# CarPC-CC-Rev3.net
KiCad netlist of a schematic drawn in EAGLE
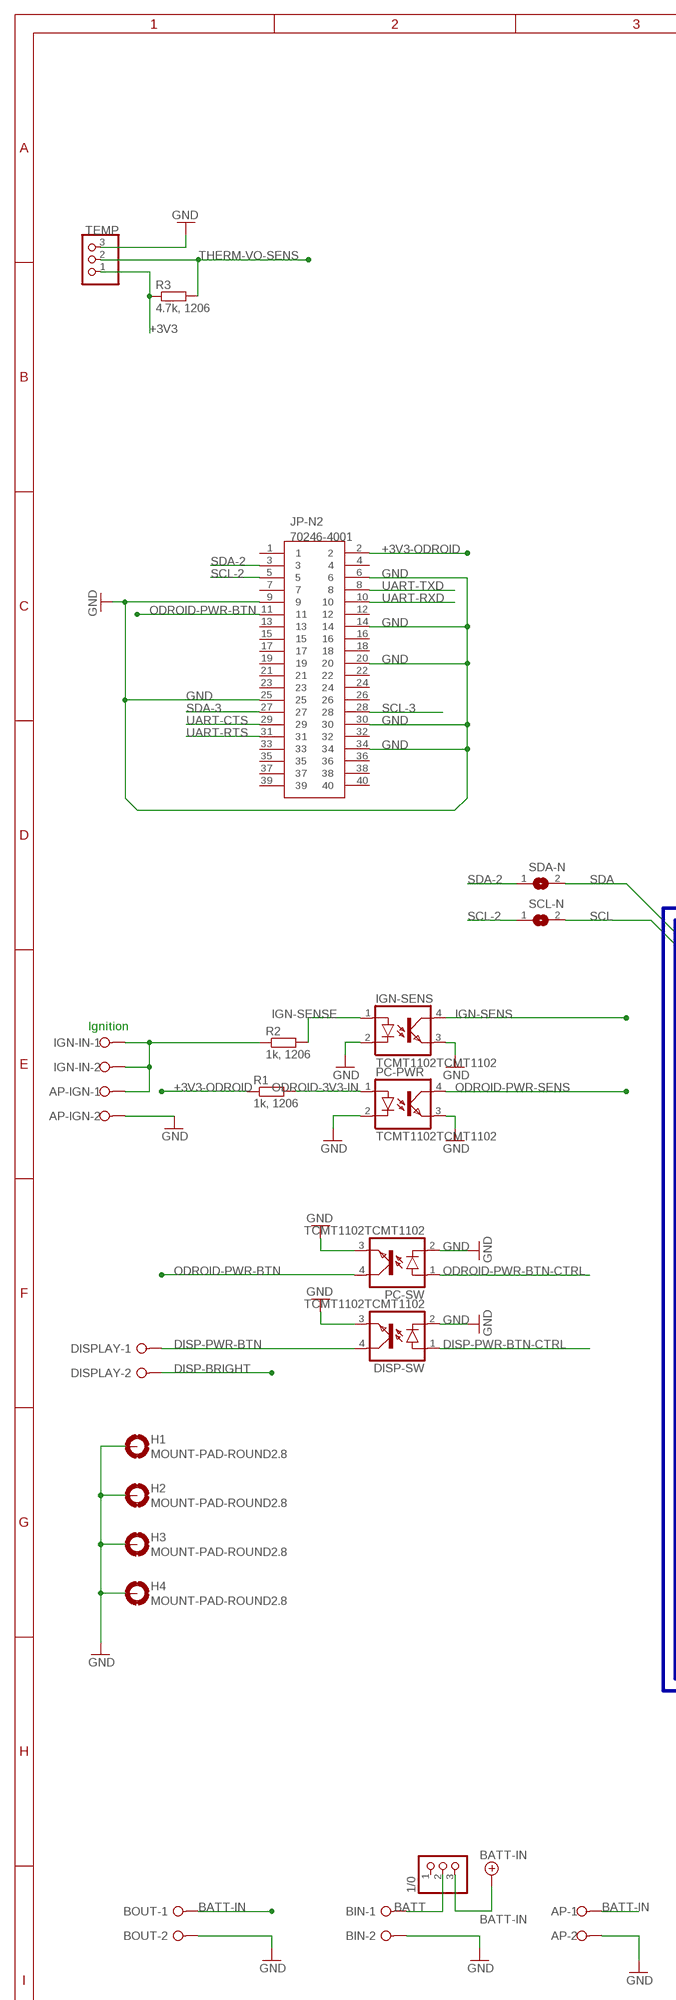
[diagram p0: schematic, sheet 1, part 1 of 2]
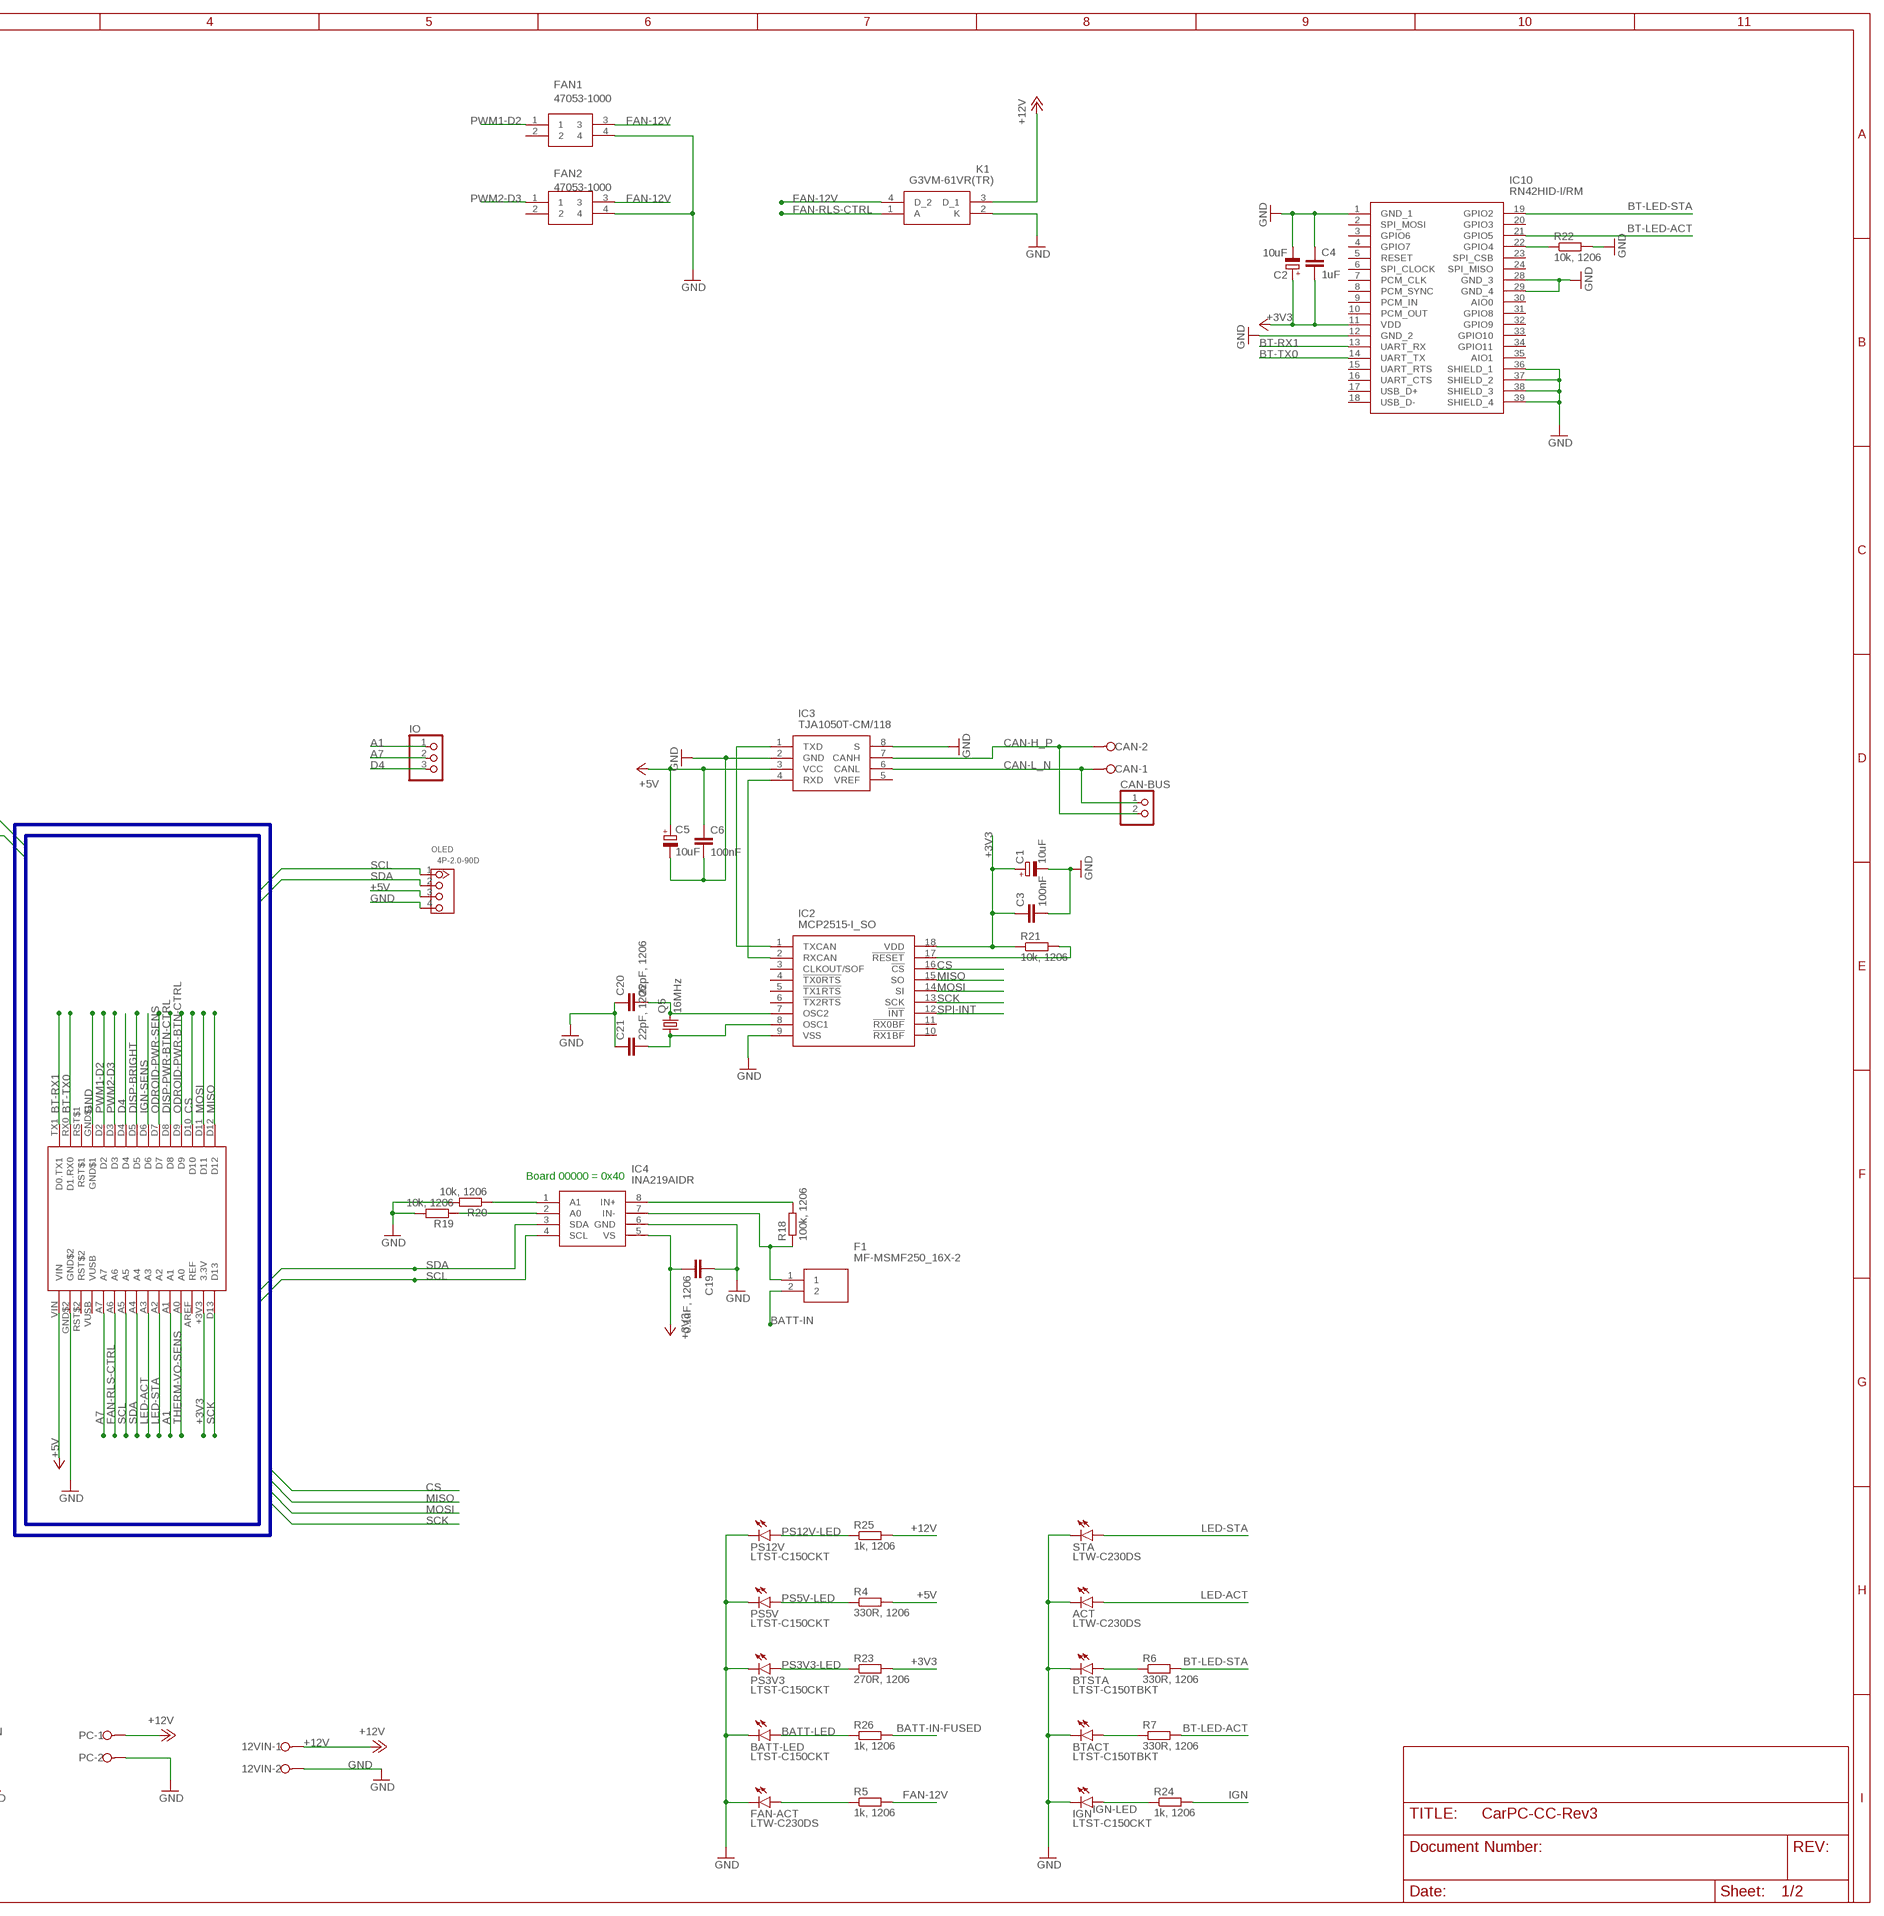
[diagram p1: schematic, sheet 1, part 2 of 2]
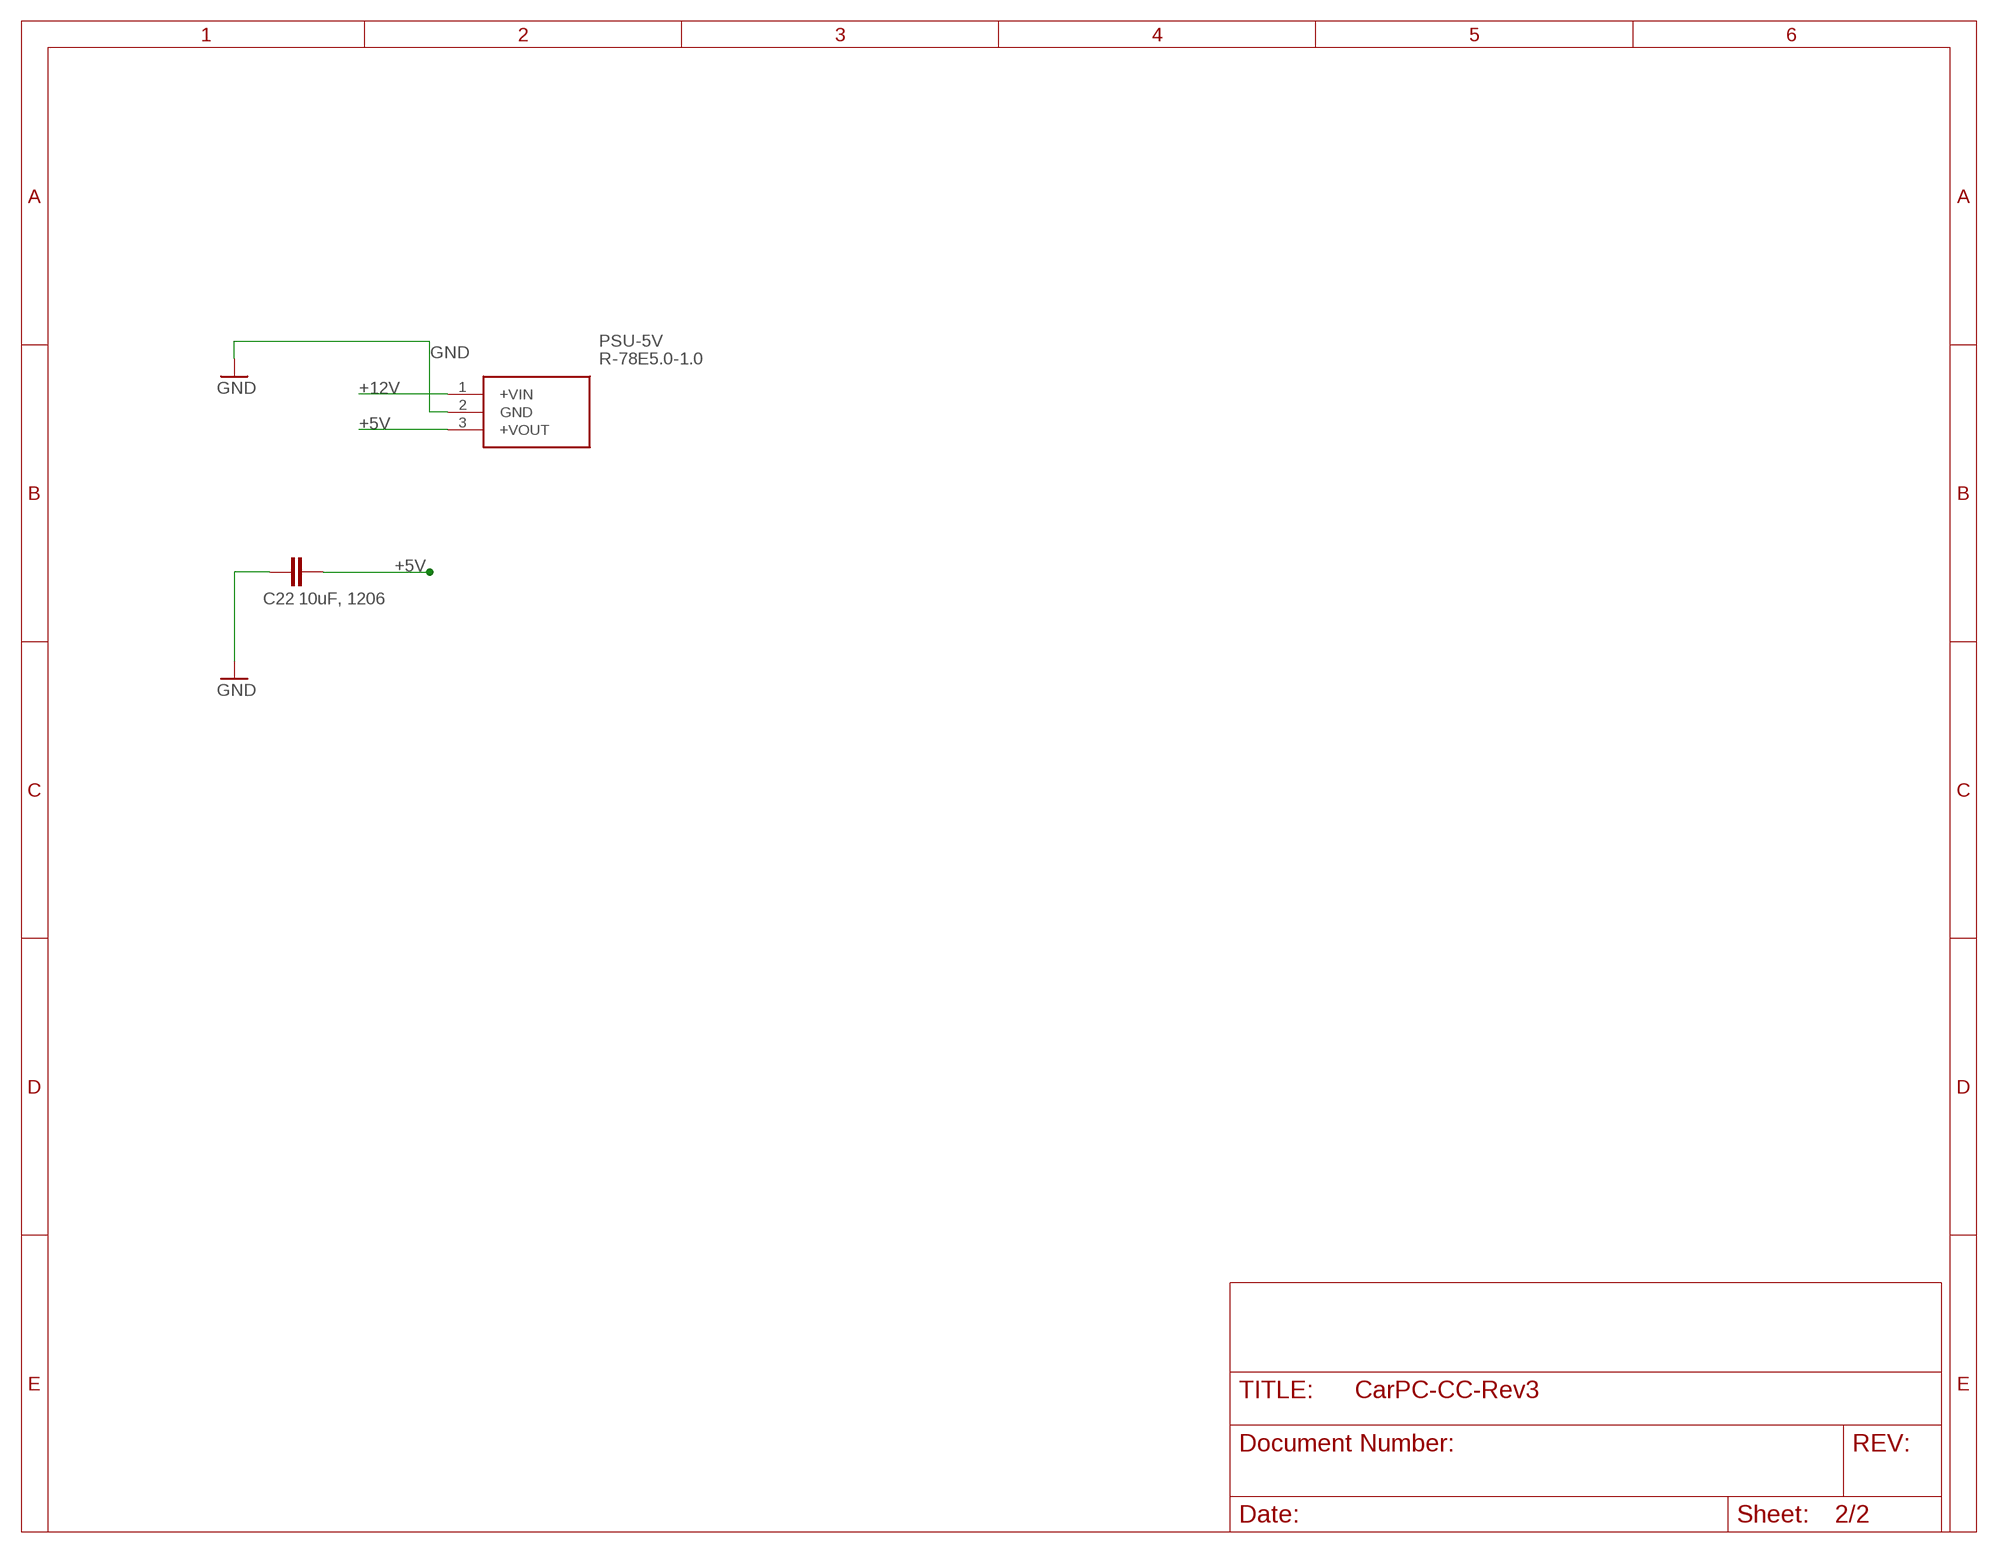
[diagram p2: schematic, sheet 2]

(export (version "E")
  (design (tool "Eeschema 10.0.6"))
  (components
    (comp (ref "1/0")
      (value "PINHD-1X3")
      (footprint "eagle-import:1X03")
      (libsource (lib "eagle-import") (part "PINHD-1X3"))
    )
    (comp (ref "12VIN")
      (value "W237-02P")
      (footprint "eagle-import:W237_132")
      (libsource (lib "eagle-import") (part "W237-02P"))
    )
    (comp (ref "ACT")
      (value "LTW-C230DS")
      (footprint "eagle-import:CHIPLED_1206")
      (libsource (lib "eagle-import") (part "LEDCHIPLED_1206"))
    )
    (comp (ref "AP")
      (value "W237-02P")
      (footprint "eagle-import:W237_132")
      (libsource (lib "eagle-import") (part "W237-02P"))
    )
    (comp (ref "AP-IGN")
      (value "W237-02P")
      (footprint "eagle-import:W237_132")
      (libsource (lib "eagle-import") (part "W237-02P"))
    )
    (comp (ref "BATT-LED")
      (value "LTST-C150CKT")
      (footprint "eagle-import:CHIPLED_1206")
      (libsource (lib "eagle-import") (part "LEDCHIPLED_1206"))
    )
    (comp (ref "BIN")
      (value "W237-02P")
      (footprint "eagle-import:W237_132")
      (libsource (lib "eagle-import") (part "W237-02P"))
    )
    (comp (ref "BOUT")
      (value "W237-02P")
      (footprint "eagle-import:W237_132")
      (libsource (lib "eagle-import") (part "W237-02P"))
    )
    (comp (ref "BTACT")
      (value "LTST-C150TBKT")
      (footprint "eagle-import:CHIPLED_1206")
      (libsource (lib "eagle-import") (part "LEDCHIPLED_1206"))
    )
    (comp (ref "BTSTA")
      (value "LTST-C150TBKT")
      (footprint "eagle-import:CHIPLED_1206")
      (libsource (lib "eagle-import") (part "LEDCHIPLED_1206"))
    )
    (comp (ref "C1")
      (value "10uF")
      (footprint "eagle-import:C1206")
      (libsource (lib "eagle-import") (part "CPOL-1206"))
    )
    (comp (ref "C2")
      (value "10uF")
      (footprint "eagle-import:C1206")
      (libsource (lib "eagle-import") (part "CPOL-1206"))
    )
    (comp (ref "C3")
      (value "100nF")
      (footprint "eagle-import:C1206")
      (libsource (lib "eagle-import") (part "C-EUC1206"))
    )
    (comp (ref "C4")
      (value "1uF")
      (footprint "eagle-import:C1206")
      (libsource (lib "eagle-import") (part "C-EUC1206"))
    )
    (comp (ref "C5")
      (value "10uF")
      (footprint "eagle-import:C1206")
      (libsource (lib "eagle-import") (part "CPOL-1206"))
    )
    (comp (ref "C6")
      (value "100nF")
      (footprint "eagle-import:C1206")
      (libsource (lib "eagle-import") (part "C-EUC1206"))
    )
    (comp (ref "C19")
      (value "0.1uF, 1206")
      (footprint "eagle-import:C1206")
      (libsource (lib "eagle-import") (part "C-EUC1206"))
    )
    (comp (ref "C20")
      (value "22pF, 1206")
      (footprint "eagle-import:C1206")
      (libsource (lib "eagle-import") (part "C-EUC1206"))
    )
    (comp (ref "C21")
      (value "22pF, 1206")
      (footprint "eagle-import:C1206")
      (libsource (lib "eagle-import") (part "C-EUC1206"))
    )
    (comp (ref "CAN")
      (value "W237-02P")
      (footprint "eagle-import:W237_132")
      (libsource (lib "eagle-import") (part "W237-02P"))
    )
    (comp (ref "CAN-BUS")
      (value "PINHD-1X2")
      (footprint "eagle-import:1X02")
      (libsource (lib "eagle-import") (part "PINHD-1X2"))
    )
    (comp (ref "DISP-SW")
      (value "TCMT1102TCMT1102")
      (footprint "eagle-import:SOIC127P700X230-4N")
      (libsource (lib "eagle-import") (part "TCMT1102TCMT1102"))
    )
    (comp (ref "DISPLAY")
      (value "W237-02P")
      (footprint "eagle-import:W237_132")
      (libsource (lib "eagle-import") (part "W237-02P"))
    )
    (comp (ref "F1")
      (value "MF-MSMF250_16X-2")
      (footprint "eagle-import:FUSC4632X160N")
      (fields
        (field (name "MANUFACTURER_PART_NUMBER") "MF-MSMF250/16X-2")
        (field (name "MOUSER_PART_NUMBER") "652-MF-MSMF250/16X-2")
        (field (name "RS_PART_NUMBER") "8978967P")
      )
      (libsource (lib "eagle-import") (part "MF-MSMF250_16X-2"))
    )
    (comp (ref "FAN-ACT")
      (value "LTW-C230DS")
      (footprint "eagle-import:CHIPLED_1206")
      (libsource (lib "eagle-import") (part "LEDCHIPLED_1206"))
    )
    (comp (ref "FAN1")
      (value "47053-1000")
      (footprint "eagle-import:47053-1000")
      (fields (field (name "MOUSER_PART_NUMBER") "538-47053-1000"))
      (libsource (lib "eagle-import") (part "47053-1000"))
    )
    (comp (ref "FAN2")
      (value "47053-1000")
      (footprint "eagle-import:47053-1000")
      (fields (field (name "MOUSER_PART_NUMBER") "538-47053-1000"))
      (libsource (lib "eagle-import") (part "47053-1000"))
    )
    (comp (ref "H1")
      (value "MOUNT-PAD-ROUND2.8")
      (footprint "eagle-import:2,8-PAD")
      (libsource (lib "eagle-import") (part "MOUNT-PAD-ROUND2.8"))
    )
    (comp (ref "H2")
      (value "MOUNT-PAD-ROUND2.8")
      (footprint "eagle-import:2,8-PAD")
      (libsource (lib "eagle-import") (part "MOUNT-PAD-ROUND2.8"))
    )
    (comp (ref "H3")
      (value "MOUNT-PAD-ROUND2.8")
      (footprint "eagle-import:2,8-PAD")
      (libsource (lib "eagle-import") (part "MOUNT-PAD-ROUND2.8"))
    )
    (comp (ref "H4")
      (value "MOUNT-PAD-ROUND2.8")
      (footprint "eagle-import:2,8-PAD")
      (libsource (lib "eagle-import") (part "MOUNT-PAD-ROUND2.8"))
    )
    (comp (ref "IC2")
      (value "MCP2515-I_SO")
      (footprint "eagle-import:SOIC127P1030X265-18N")
      (fields
        (field (name "MANUFACTURER_PART_NUMBER") "MCP2515-I/SO")
        (field (name "MOUSER_PART_NUMBER") "579-MCP2515-I/SO")
      )
      (libsource (lib "eagle-import") (part "MCP2515-I_SO"))
    )
    (comp (ref "IC3")
      (value "TJA1050T-CM/118")
      (footprint "eagle-import:SOIC127P600X175-8N")
      (fields
        (field (name "MANUFACTURER_PART_NUMBER") "TJA1050T/CM,118")
        (field (name "MOUSER_PART_NUMBER") "771-TJA1050T/CM118")
      )
      (libsource (lib "eagle-import") (part "TJA1050T_CM,118"))
    )
    (comp (ref "IC4")
      (value "INA219AIDR")
      (footprint "eagle-import:SOIC127P600X175-8N")
      (fields (field (name "MOUSER_PART_NUMBER") "595-INA219AIDR"))
      (libsource (lib "eagle-import") (part "INA219AIDR"))
    )
    (comp (ref "IC10")
      (value "RN42HID-I/RM")
      (footprint "eagle-import:RN42HIDIRM")
      (fields
        (field (name "MOUSER_PART_NUMBER") "765-RN42HID-I/RM")
        (field (name "RS_PART_NUMBER") "9123020")
      )
      (libsource (lib "eagle-import") (part "RN42HID-I_RM"))
    )
    (comp (ref "IGN")
      (value "LTST-C150CKT")
      (footprint "eagle-import:CHIPLED_1206")
      (libsource (lib "eagle-import") (part "LEDCHIPLED_1206"))
    )
    (comp (ref "IGN-IN")
      (value "W237-02P")
      (footprint "eagle-import:W237_132")
      (libsource (lib "eagle-import") (part "W237-02P"))
    )
    (comp (ref "IGN-SENS")
      (value "TCMT1102TCMT1102")
      (footprint "eagle-import:SOIC127P700X230-4N")
      (libsource (lib "eagle-import") (part "TCMT1102TCMT1102"))
    )
    (comp (ref "IO")
      (value "PINHD-1X3")
      (footprint "eagle-import:1X03")
      (libsource (lib "eagle-import") (part "PINHD-1X3"))
    )
    (comp (ref "JP-N2")
      (value "70246-4001")
      (footprint "eagle-import:SHDR40W94P254_2X20_5842X889X92")
      (fields (field (name "MOUSER_PART_NUMBER") "538-70246-4001") (field (name "RS_PART_NUMBER") "6701825P"))
      (libsource (lib "eagle-import") (part "70246-4001"))
    )
    (comp (ref "K1")
      (value "G3VM-61VR(TR)")
      (footprint "eagle-import:G3VM61VRTR")
      (fields (field (name "MOUSER_PART_NUMBER") "653-G3VM-61VRTR"))
      (libsource (lib "eagle-import") (part "G3VM-61VR(TR)"))
    )
    (comp (ref "NANO_33_IOT")
      (value "Arduino-Nano-33-IOT")
      (footprint "eagle-import:ARDNANO33IOT_SMD")
      (libsource (lib "eagle-import") (part "ARDUINONANO33IOTARDUINONANO33IOT_SMD"))
    )
    (comp (ref "OLED")
      (value "4P-2.0-90D")
      (footprint "eagle-import:HW4-2.0-90D")
      (libsource (lib "eagle-import") (part "GROVE-CONNECTOR-DIP-90D(4P-2.0)"))
    )
    (comp (ref "PC")
      (value "W237-02P")
      (footprint "eagle-import:W237_132")
      (libsource (lib "eagle-import") (part "W237-02P"))
    )
    (comp (ref "PC-PWR")
      (value "TCMT1102TCMT1102")
      (footprint "eagle-import:SOIC127P700X230-4N")
      (libsource (lib "eagle-import") (part "TCMT1102TCMT1102"))
    )
    (comp (ref "PC-SW")
      (value "TCMT1102TCMT1102")
      (footprint "eagle-import:SOIC127P700X230-4N")
      (libsource (lib "eagle-import") (part "TCMT1102TCMT1102"))
    )
    (comp (ref "PS3V3")
      (value "LTST-C150CKT")
      (footprint "eagle-import:CHIPLED_1206")
      (libsource (lib "eagle-import") (part "LEDCHIPLED_1206"))
    )
    (comp (ref "PS5V")
      (value "LTST-C150CKT")
      (footprint "eagle-import:CHIPLED_1206")
      (libsource (lib "eagle-import") (part "LEDCHIPLED_1206"))
    )
    (comp (ref "PS12V")
      (value "LTST-C150CKT")
      (footprint "eagle-import:CHIPLED_1206")
      (libsource (lib "eagle-import") (part "LEDCHIPLED_1206"))
    )
    (comp (ref "Q5")
      (value "16MHz")
      (footprint "eagle-import:HC49-S")
      (libsource (lib "eagle-import") (part "CRYSTALHC49S"))
    )
    (comp (ref "R1")
      (value "1k, 1206")
      (footprint "eagle-import:R1206")
      (libsource (lib "eagle-import") (part "R-EU_R1206"))
    )
    (comp (ref "R2")
      (value "1k, 1206")
      (footprint "eagle-import:R1206")
      (libsource (lib "eagle-import") (part "R-EU_R1206"))
    )
    (comp (ref "R3")
      (value "4.7k, 1206")
      (footprint "eagle-import:R1206")
      (libsource (lib "eagle-import") (part "R-EU_R1206"))
    )
    (comp (ref "R4")
      (value "330R, 1206")
      (footprint "eagle-import:R1206")
      (libsource (lib "eagle-import") (part "R-EU_R1206"))
    )
    (comp (ref "R5")
      (value "1k, 1206")
      (footprint "eagle-import:R1206")
      (libsource (lib "eagle-import") (part "R-EU_R1206"))
    )
    (comp (ref "R6")
      (value "330R, 1206")
      (footprint "eagle-import:R1206")
      (libsource (lib "eagle-import") (part "R-EU_R1206"))
    )
    (comp (ref "R7")
      (value "330R, 1206")
      (footprint "eagle-import:R1206")
      (libsource (lib "eagle-import") (part "R-EU_R1206"))
    )
    (comp (ref "R18")
      (value "100k, 1206")
      (footprint "eagle-import:R1206")
      (libsource (lib "eagle-import") (part "R-EU_R1206"))
    )
    (comp (ref "R19")
      (value "10k, 1206")
      (footprint "eagle-import:R1206")
      (libsource (lib "eagle-import") (part "R-EU_R1206"))
    )
    (comp (ref "R20")
      (value "10k, 1206")
      (footprint "eagle-import:R1206")
      (libsource (lib "eagle-import") (part "R-EU_R1206"))
    )
    (comp (ref "R21")
      (value "10k, 1206")
      (footprint "eagle-import:R1206")
      (libsource (lib "eagle-import") (part "R-EU_R1206"))
    )
    (comp (ref "R22")
      (value "10k, 1206")
      (footprint "eagle-import:R1206")
      (libsource (lib "eagle-import") (part "R-EU_R1206"))
    )
    (comp (ref "R23")
      (value "270R, 1206")
      (footprint "eagle-import:R1206")
      (libsource (lib "eagle-import") (part "R-EU_R1206"))
    )
    (comp (ref "R24")
      (value "1k, 1206")
      (footprint "eagle-import:R1206")
      (libsource (lib "eagle-import") (part "R-EU_R1206"))
    )
    (comp (ref "R25")
      (value "1k, 1206")
      (footprint "eagle-import:R1206")
      (libsource (lib "eagle-import") (part "R-EU_R1206"))
    )
    (comp (ref "R26")
      (value "1k, 1206")
      (footprint "eagle-import:R1206")
      (libsource (lib "eagle-import") (part "R-EU_R1206"))
    )
    (comp (ref "SCL-N")
      (value "SJ")
      (footprint "eagle-import:SJ")
      (libsource (lib "eagle-import") (part "SJ"))
    )
    (comp (ref "SDA-N")
      (value "SJ")
      (footprint "eagle-import:SJ")
      (libsource (lib "eagle-import") (part "SJ"))
    )
    (comp (ref "STA")
      (value "LTW-C230DS")
      (footprint "eagle-import:CHIPLED_1206")
      (libsource (lib "eagle-import") (part "LEDCHIPLED_1206"))
    )
    (comp (ref "TEMP")
      (value "PINHD-1X3/90")
      (footprint "eagle-import:1X03_90")
      (libsource (lib "eagle-import") (part "PINHD-1X3/90"))
    )
    (comp (ref "C22")
      (value "10uF, 1206")
      (footprint "eagle-import:C1206")
      (libsource (lib "eagle-import") (part "C-EUC1206"))
    )
    (comp (ref "PSU-5V")
      (value "R-78E5.0-1.0")
      (footprint "eagle-import:R-78E5.0-1.0")
      (fields
        (field (name "MOUSER_PART_NUMBER") "919-R-78E5.0-1.0")
        (field (name "RS_PART_NUMBER") "1446290P")
      )
      (libsource (lib "eagle-import") (part "R-78E5.0-1.0"))
    )
  )
  (nets
    (net (code "1") (name "+3V3") (class "Default")
      (node (ref "C1") (pin "1") (pinfunction "+_1") (pintype "passive"))
      (node (ref "C19") (pin "2") (pinfunction "2_2") (pintype "passive"))
      (node (ref "C2") (pin "1") (pinfunction "+_1") (pintype "passive"))
      (node (ref "C3") (pin "1") (pinfunction "1_1") (pintype "passive"))
      (node (ref "C4") (pin "2") (pinfunction "2_2") (pintype "passive"))
      (node (ref "IC10") (pin "11") (pinfunction "VDD_11") (pintype "bidirectional"))
      (node (ref "IC2") (pin "18") (pinfunction "VDD_18") (pintype "power_in"))
      (node (ref "IC4") (pin "5") (pinfunction "VS_5") (pintype "bidirectional"))
      (node (ref "NANO_33_IOT") (pin "+3V3") (pinfunction "3.3V_+3V3") (pintype "bidirectional"))
      (node (ref "R21") (pin "1") (pinfunction "1_1") (pintype "passive"))
      (node (ref "R23") (pin "2") (pinfunction "2_2") (pintype "passive"))
      (node (ref "R3") (pin "1") (pinfunction "1_1") (pintype "passive"))
      (node (ref "TEMP") (pin "1") (pinfunction "1_1") (pintype "passive"))
    )
    (net (code "2") (name "+3V3-ODROID") (class "Default")
      (node (ref "JP-N2") (pin "2") (pinfunction "2_2") (pintype "bidirectional"))
      (node (ref "R1") (pin "1") (pinfunction "1_1") (pintype "passive"))
    )
    (net (code "3") (name "+5V") (class "Default")
      (node (ref "C22") (pin "2") (pinfunction "2_2") (pintype "passive"))
      (node (ref "C5") (pin "1") (pinfunction "+_1") (pintype "passive"))
      (node (ref "C6") (pin "1") (pinfunction "1_1") (pintype "passive"))
      (node (ref "IC3") (pin "3") (pinfunction "VCC_3") (pintype "bidirectional"))
      (node (ref "NANO_33_IOT") (pin "VIN") (pinfunction "VIN_VIN") (pintype "bidirectional"))
      (node (ref "OLED") (pin "3") (pinfunction "3_3") (pintype "bidirectional"))
      (node (ref "PSU-5V") (pin "3") (pinfunction "+VOUT_3") (pintype "bidirectional"))
      (node (ref "R4") (pin "2") (pinfunction "2_2") (pintype "passive"))
    )
    (net (code "4") (name "+12V") (class "Default")
      (node (ref "12VIN") (pin "1") (pinfunction "KL_1") (pintype "passive"))
      (node (ref "K1") (pin "3") (pinfunction "D_1_3") (pintype "bidirectional"))
      (node (ref "PC") (pin "1") (pinfunction "KL_1") (pintype "passive"))
      (node (ref "PSU-5V") (pin "1") (pinfunction "+VIN_1") (pintype "bidirectional"))
      (node (ref "R25") (pin "2") (pinfunction "2_2") (pintype "passive"))
    )
    (net (code "5") (name "A1") (class "Default")
      (node (ref "IO") (pin "1") (pinfunction "1_1") (pintype "passive"))
      (node (ref "NANO_33_IOT") (pin "A1") (pinfunction "A1_A1") (pintype "bidirectional"))
    )
    (net (code "6") (name "A7") (class "Default")
      (node (ref "IO") (pin "2") (pinfunction "2_2") (pintype "passive"))
      (node (ref "NANO_33_IOT") (pin "A7") (pinfunction "A7_A7") (pintype "bidirectional"))
    )
    (net (code "7") (name "BATT") (class "Default")
      (node (ref "1/0") (pin "2") (pinfunction "2_2") (pintype "passive"))
      (node (ref "BIN") (pin "1") (pinfunction "KL_1") (pintype "passive"))
    )
    (net (code "8") (name "BATT-IN") (class "Default")
      (node (ref "1/0") (pin "3") (pinfunction "3_3") (pintype "passive"))
      (node (ref "AP") (pin "1") (pinfunction "KL_1") (pintype "passive"))
      (node (ref "BOUT") (pin "1") (pinfunction "KL_1") (pintype "passive"))
      (node (ref "F1") (pin "2") (pinfunction "2_2") (pintype "bidirectional"))
    )
    (net (code "9") (name "BATT-IN-FUSED") (class "Default")
      (node (ref "F1") (pin "1") (pinfunction "1_1") (pintype "bidirectional"))
      (node (ref "IC4") (pin "7") (pinfunction "IN-_7") (pintype "bidirectional"))
      (node (ref "R18") (pin "1") (pinfunction "1_1") (pintype "passive"))
      (node (ref "R26") (pin "2") (pinfunction "2_2") (pintype "passive"))
    )
    (net (code "10") (name "BATT-LED") (class "Default")
      (node (ref "BATT-LED") (pin "A") (pinfunction "A_A") (pintype "passive"))
      (node (ref "R26") (pin "1") (pinfunction "1_1") (pintype "passive"))
    )
    (net (code "11") (name "BT-LED-ACT") (class "Default")
      (node (ref "IC10") (pin "21") (pinfunction "GPIO5_21") (pintype "bidirectional"))
      (node (ref "R7") (pin "2") (pinfunction "2_2") (pintype "passive"))
    )
    (net (code "12") (name "BT-LED-STA") (class "Default")
      (node (ref "IC10") (pin "19") (pinfunction "GPIO2_19") (pintype "bidirectional"))
      (node (ref "R6") (pin "2") (pinfunction "2_2") (pintype "passive"))
    )
    (net (code "13") (name "BT-RX1") (class "Default")
      (node (ref "IC10") (pin "13") (pinfunction "UART_RX_13") (pintype "bidirectional"))
      (node (ref "NANO_33_IOT") (pin "TX1") (pinfunction "D0.TX1_TX1") (pintype "bidirectional"))
    )
    (net (code "14") (name "BT-TX0") (class "Default")
      (node (ref "IC10") (pin "14") (pinfunction "UART_TX_14") (pintype "bidirectional"))
      (node (ref "NANO_33_IOT") (pin "RX0") (pinfunction "D1.RX0_RX0") (pintype "bidirectional"))
    )
    (net (code "15") (name "CAN-H_P") (class "Default")
      (node (ref "CAN") (pin "2") (pinfunction "KL_2") (pintype "passive"))
      (node (ref "CAN-BUS") (pin "2") (pinfunction "2_2") (pintype "passive"))
      (node (ref "IC3") (pin "7") (pinfunction "CANH_7") (pintype "bidirectional"))
    )
    (net (code "16") (name "CAN-L_N") (class "Default")
      (node (ref "CAN") (pin "1") (pinfunction "KL_1") (pintype "passive"))
      (node (ref "CAN-BUS") (pin "1") (pinfunction "1_1") (pintype "passive"))
      (node (ref "IC3") (pin "6") (pinfunction "CANL_6") (pintype "bidirectional"))
    )
    (net (code "17") (name "CS") (class "Default")
      (node (ref "IC2") (pin "16") (pinfunction "~{CS}_16") (pintype "input"))
      (node (ref "NANO_33_IOT") (pin "D10") (pinfunction "D10_D10") (pintype "bidirectional"))
    )
    (net (code "18") (name "D4") (class "Default")
      (node (ref "IO") (pin "3") (pinfunction "3_3") (pintype "passive"))
      (node (ref "NANO_33_IOT") (pin "D4") (pinfunction "D4_D4") (pintype "bidirectional"))
    )
    (net (code "19") (name "DISP-BRIGHT") (class "Default")
      (node (ref "DISPLAY") (pin "2") (pinfunction "KL_2") (pintype "passive"))
      (node (ref "NANO_33_IOT") (pin "D5") (pinfunction "D5_D5") (pintype "bidirectional"))
    )
    (net (code "20") (name "DISP-PWR-BTN") (class "Default")
      (node (ref "DISP-SW") (pin "4") (pinfunction "COL_4") (pintype "passive"))
      (node (ref "DISPLAY") (pin "1") (pinfunction "KL_1") (pintype "passive"))
    )
    (net (code "21") (name "DISP-PWR-BTN-CTRL") (class "Default")
      (node (ref "DISP-SW") (pin "1") (pinfunction "A_1") (pintype "passive"))
      (node (ref "NANO_33_IOT") (pin "D8") (pinfunction "D8_D8") (pintype "bidirectional"))
    )
    (net (code "22") (name "FAN-12V") (class "Default")
      (node (ref "FAN1") (pin "3") (pinfunction "3_3") (pintype "bidirectional"))
      (node (ref "FAN2") (pin "3") (pinfunction "3_3") (pintype "bidirectional"))
      (node (ref "K1") (pin "4") (pinfunction "D_2_4") (pintype "bidirectional"))
      (node (ref "R5") (pin "2") (pinfunction "2_2") (pintype "passive"))
    )
    (net (code "23") (name "FAN-RLS-CTRL") (class "Default")
      (node (ref "K1") (pin "1") (pinfunction "A_1") (pintype "bidirectional"))
      (node (ref "NANO_33_IOT") (pin "A6") (pinfunction "A6_A6") (pintype "bidirectional"))
    )
    (net (code "24") (name "GND") (class "Default")
      (node (ref "12VIN") (pin "2") (pinfunction "KL_2") (pintype "passive"))
      (node (ref "ACT") (pin "C") (pinfunction "C_C") (pintype "passive"))
      (node (ref "AP") (pin "2") (pinfunction "KL_2") (pintype "passive"))
      (node (ref "AP-IGN") (pin "2") (pinfunction "KL_2") (pintype "passive"))
      (node (ref "BATT-LED") (pin "C") (pinfunction "C_C") (pintype "passive"))
      (node (ref "BIN") (pin "2") (pinfunction "KL_2") (pintype "passive"))
      (node (ref "BOUT") (pin "2") (pinfunction "KL_2") (pintype "passive"))
      (node (ref "BTACT") (pin "C") (pinfunction "C_C") (pintype "passive"))
      (node (ref "BTSTA") (pin "C") (pinfunction "C_C") (pintype "passive"))
      (node (ref "C1") (pin "2") (pinfunction "-_2") (pintype "passive"))
      (node (ref "C19") (pin "1") (pinfunction "1_1") (pintype "passive"))
      (node (ref "C2") (pin "2") (pinfunction "-_2") (pintype "passive"))
      (node (ref "C20") (pin "1") (pinfunction "1_1") (pintype "passive"))
      (node (ref "C21") (pin "1") (pinfunction "1_1") (pintype "passive"))
      (node (ref "C22") (pin "1") (pinfunction "1_1") (pintype "passive"))
      (node (ref "C3") (pin "2") (pinfunction "2_2") (pintype "passive"))
      (node (ref "C4") (pin "1") (pinfunction "1_1") (pintype "passive"))
      (node (ref "C5") (pin "2") (pinfunction "-_2") (pintype "passive"))
      (node (ref "C6") (pin "2") (pinfunction "2_2") (pintype "passive"))
      (node (ref "DISP-SW") (pin "2") (pinfunction "K_2") (pintype "passive"))
      (node (ref "DISP-SW") (pin "3") (pinfunction "EMI_3") (pintype "passive"))
      (node (ref "FAN-ACT") (pin "C") (pinfunction "C_C") (pintype "passive"))
      (node (ref "FAN1") (pin "4") (pinfunction "4_4") (pintype "bidirectional"))
      (node (ref "FAN2") (pin "4") (pinfunction "4_4") (pintype "bidirectional"))
      (node (ref "H1") (pin "B2,8") (pinfunction "MOUNT_B2,8") (pintype "passive"))
      (node (ref "H2") (pin "B2,8") (pinfunction "MOUNT_B2,8") (pintype "passive"))
      (node (ref "H3") (pin "B2,8") (pinfunction "MOUNT_B2,8") (pintype "passive"))
      (node (ref "H4") (pin "B2,8") (pinfunction "MOUNT_B2,8") (pintype "passive"))
      (node (ref "IC10") (pin "1") (pinfunction "GND_1_1") (pintype "bidirectional"))
      (node (ref "IC10") (pin "12") (pinfunction "GND_2_12") (pintype "bidirectional"))
      (node (ref "IC10") (pin "28") (pinfunction "GND_3_28") (pintype "bidirectional"))
      (node (ref "IC10") (pin "29") (pinfunction "GND_4_29") (pintype "bidirectional"))
      (node (ref "IC10") (pin "36") (pinfunction "SHIELD_1_36") (pintype "bidirectional"))
      (node (ref "IC10") (pin "37") (pinfunction "SHIELD_2_37") (pintype "bidirectional"))
      (node (ref "IC10") (pin "38") (pinfunction "SHIELD_3_38") (pintype "bidirectional"))
      (node (ref "IC10") (pin "39") (pinfunction "SHIELD_4_39") (pintype "bidirectional"))
      (node (ref "IC2") (pin "9") (pinfunction "VSS_9") (pintype "power_in"))
      (node (ref "IC3") (pin "2") (pinfunction "GND_2") (pintype "bidirectional"))
      (node (ref "IC3") (pin "8") (pinfunction "S_8") (pintype "bidirectional"))
      (node (ref "IC4") (pin "6") (pinfunction "GND_6") (pintype "bidirectional"))
      (node (ref "IGN") (pin "C") (pinfunction "C_C") (pintype "passive"))
      (node (ref "IGN-SENS") (pin "2") (pinfunction "K_2") (pintype "passive"))
      (node (ref "IGN-SENS") (pin "3") (pinfunction "EMI_3") (pintype "passive"))
      (node (ref "JP-N2") (pin "14") (pinfunction "14_14") (pintype "bidirectional"))
      (node (ref "JP-N2") (pin "20") (pinfunction "20_20") (pintype "bidirectional"))
      (node (ref "JP-N2") (pin "25") (pinfunction "25_25") (pintype "bidirectional"))
      (node (ref "JP-N2") (pin "30") (pinfunction "30_30") (pintype "bidirectional"))
      (node (ref "JP-N2") (pin "34") (pinfunction "34_34") (pintype "bidirectional"))
      (node (ref "JP-N2") (pin "6") (pinfunction "6_6") (pintype "bidirectional"))
      (node (ref "JP-N2") (pin "9") (pinfunction "9_9") (pintype "bidirectional"))
      (node (ref "K1") (pin "2") (pinfunction "K_2") (pintype "bidirectional"))
      (node (ref "NANO_33_IOT") (pin "GND$1") (pinfunction "GND$1_GND$1") (pintype "bidirectional"))
      (node (ref "NANO_33_IOT") (pin "GND$2") (pinfunction "GND$2_GND$2") (pintype "bidirectional"))
      (node (ref "OLED") (pin "4") (pinfunction "4_4") (pintype "bidirectional"))
      (node (ref "PC") (pin "2") (pinfunction "KL_2") (pintype "passive"))
      (node (ref "PC-PWR") (pin "2") (pinfunction "K_2") (pintype "passive"))
      (node (ref "PC-PWR") (pin "3") (pinfunction "EMI_3") (pintype "passive"))
      (node (ref "PC-SW") (pin "2") (pinfunction "K_2") (pintype "passive"))
      (node (ref "PC-SW") (pin "3") (pinfunction "EMI_3") (pintype "passive"))
      (node (ref "PS12V") (pin "C") (pinfunction "C_C") (pintype "passive"))
      (node (ref "PS3V3") (pin "C") (pinfunction "C_C") (pintype "passive"))
      (node (ref "PS5V") (pin "C") (pinfunction "C_C") (pintype "passive"))
      (node (ref "PSU-5V") (pin "2") (pinfunction "GND_2") (pintype "bidirectional"))
      (node (ref "R19") (pin "2") (pinfunction "2_2") (pintype "passive"))
      (node (ref "R20") (pin "2") (pinfunction "2_2") (pintype "passive"))
      (node (ref "R22") (pin "2") (pinfunction "2_2") (pintype "passive"))
      (node (ref "STA") (pin "C") (pinfunction "C_C") (pintype "passive"))
      (node (ref "TEMP") (pin "3") (pinfunction "3_3") (pintype "passive"))
    )
    (net (code "25") (name "IGN") (class "Default")
      (node (ref "AP-IGN") (pin "1") (pinfunction "KL_1") (pintype "passive"))
      (node (ref "IGN-IN") (pin "1") (pinfunction "KL_1") (pintype "passive"))
      (node (ref "IGN-IN") (pin "2") (pinfunction "KL_2") (pintype "passive"))
      (node (ref "R2") (pin "1") (pinfunction "1_1") (pintype "passive"))
      (node (ref "R24") (pin "2") (pinfunction "2_2") (pintype "passive"))
    )
    (net (code "26") (name "IGN-LED") (class "Default")
      (node (ref "IGN") (pin "A") (pinfunction "A_A") (pintype "passive"))
      (node (ref "R24") (pin "1") (pinfunction "1_1") (pintype "passive"))
    )
    (net (code "27") (name "IGN-SENS") (class "Default")
      (node (ref "IGN-SENS") (pin "4") (pinfunction "COL_4") (pintype "passive"))
      (node (ref "NANO_33_IOT") (pin "D6") (pinfunction "D6_D6") (pintype "bidirectional"))
    )
    (net (code "28") (name "IGN-SENSE") (class "Default")
      (node (ref "IGN-SENS") (pin "1") (pinfunction "A_1") (pintype "passive"))
      (node (ref "R2") (pin "2") (pinfunction "2_2") (pintype "passive"))
    )
    (net (code "29") (name "LED-ACT") (class "Default")
      (node (ref "ACT") (pin "A") (pinfunction "A_A") (pintype "passive"))
      (node (ref "NANO_33_IOT") (pin "A3") (pinfunction "A3_A3") (pintype "bidirectional"))
    )
    (net (code "30") (name "LED-STA") (class "Default")
      (node (ref "NANO_33_IOT") (pin "A2") (pinfunction "A2_A2") (pintype "bidirectional"))
      (node (ref "STA") (pin "A") (pinfunction "A_A") (pintype "passive"))
    )
    (net (code "31") (name "MISO") (class "Default")
      (node (ref "IC2") (pin "15") (pinfunction "SO_15") (pintype "bidirectional"))
      (node (ref "NANO_33_IOT") (pin "D12") (pinfunction "D12_D12") (pintype "bidirectional"))
    )
    (net (code "32") (name "MOSI") (class "Default")
      (node (ref "IC2") (pin "14") (pinfunction "SI_14") (pintype "bidirectional"))
      (node (ref "NANO_33_IOT") (pin "D11") (pinfunction "D11_D11") (pintype "bidirectional"))
    )
    (net (code "33") (name "Net-(BTACT-PadA)") (class "Default")
      (node (ref "BTACT") (pin "A") (pinfunction "A_A") (pintype "passive"))
      (node (ref "R7") (pin "1") (pinfunction "1_1") (pintype "passive"))
    )
    (net (code "34") (name "Net-(BTSTA-PadA)") (class "Default")
      (node (ref "BTSTA") (pin "A") (pinfunction "A_A") (pintype "passive"))
      (node (ref "R6") (pin "1") (pinfunction "1_1") (pintype "passive"))
    )
    (net (code "35") (name "Net-(FAN-ACT-PadA)") (class "Default")
      (node (ref "FAN-ACT") (pin "A") (pinfunction "A_A") (pintype "passive"))
      (node (ref "R5") (pin "1") (pinfunction "1_1") (pintype "passive"))
    )
    (net (code "36") (name "Net-(IC2-OSC1)") (class "Default")
      (node (ref "C21") (pin "2") (pinfunction "2_2") (pintype "passive"))
      (node (ref "IC2") (pin "8") (pinfunction "OSC1_8") (pintype "bidirectional"))
      (node (ref "Q5") (pin "1") (pinfunction "1_1") (pintype "passive"))
    )
    (net (code "37") (name "Net-(IC2-OSC2)") (class "Default")
      (node (ref "C20") (pin "2") (pinfunction "2_2") (pintype "passive"))
      (node (ref "IC2") (pin "7") (pinfunction "OSC2_7") (pintype "bidirectional"))
      (node (ref "Q5") (pin "2") (pinfunction "2_2") (pintype "passive"))
    )
    (net (code "38") (name "Net-(IC2-RXCAN)") (class "Default")
      (node (ref "IC2") (pin "2") (pinfunction "RXCAN_2") (pintype "bidirectional"))
      (node (ref "IC3") (pin "4") (pinfunction "RXD_4") (pintype "bidirectional"))
    )
    (net (code "39") (name "Net-(IC2-TXCAN)") (class "Default")
      (node (ref "IC2") (pin "1") (pinfunction "TXCAN_1") (pintype "bidirectional"))
      (node (ref "IC3") (pin "1") (pinfunction "TXD_1") (pintype "bidirectional"))
    )
    (net (code "40") (name "Net-(IC2-~{RESET})") (class "Default")
      (node (ref "IC2") (pin "17") (pinfunction "~{RESET}_17") (pintype "bidirectional"))
      (node (ref "R21") (pin "2") (pinfunction "2_2") (pintype "passive"))
    )
    (net (code "41") (name "Net-(IC4-A0)") (class "Default")
      (node (ref "IC4") (pin "2") (pinfunction "A0_2") (pintype "bidirectional"))
      (node (ref "R19") (pin "1") (pinfunction "1_1") (pintype "passive"))
    )
    (net (code "42") (name "Net-(IC4-A1)") (class "Default")
      (node (ref "IC4") (pin "1") (pinfunction "A1_1") (pintype "bidirectional"))
      (node (ref "R20") (pin "1") (pinfunction "1_1") (pintype "passive"))
    )
    (net (code "43") (name "Net-(IC4-IN+)") (class "Default")
      (node (ref "IC4") (pin "8") (pinfunction "IN+_8") (pintype "bidirectional"))
      (node (ref "R18") (pin "2") (pinfunction "2_2") (pintype "passive"))
    )
    (net (code "44") (name "Net-(IC10-GPIO4)") (class "Default")
      (node (ref "IC10") (pin "22") (pinfunction "GPIO4_22") (pintype "bidirectional"))
      (node (ref "R22") (pin "1") (pinfunction "1_1") (pintype "passive"))
    )
    (net (code "45") (name "ODROID-3V3-IN") (class "Default")
      (node (ref "PC-PWR") (pin "1") (pinfunction "A_1") (pintype "passive"))
      (node (ref "R1") (pin "2") (pinfunction "2_2") (pintype "passive"))
    )
    (net (code "46") (name "ODROID-PWR-BTN") (class "Default")
      (node (ref "JP-N2") (pin "11") (pinfunction "11_11") (pintype "bidirectional"))
      (node (ref "PC-SW") (pin "4") (pinfunction "COL_4") (pintype "passive"))
    )
    (net (code "47") (name "ODROID-PWR-BTN-CTRL") (class "Default")
      (node (ref "NANO_33_IOT") (pin "D9") (pinfunction "D9_D9") (pintype "bidirectional"))
      (node (ref "PC-SW") (pin "1") (pinfunction "A_1") (pintype "passive"))
    )
    (net (code "48") (name "ODROID-PWR-SENS") (class "Default")
      (node (ref "NANO_33_IOT") (pin "D7") (pinfunction "D7_D7") (pintype "bidirectional"))
      (node (ref "PC-PWR") (pin "4") (pinfunction "COL_4") (pintype "passive"))
    )
    (net (code "49") (name "PS3V3-LED") (class "Default")
      (node (ref "PS3V3") (pin "A") (pinfunction "A_A") (pintype "passive"))
      (node (ref "R23") (pin "1") (pinfunction "1_1") (pintype "passive"))
    )
    (net (code "50") (name "PS5V-LED") (class "Default")
      (node (ref "PS5V") (pin "A") (pinfunction "A_A") (pintype "passive"))
      (node (ref "R4") (pin "1") (pinfunction "1_1") (pintype "passive"))
    )
    (net (code "51") (name "PS12V-LED") (class "Default")
      (node (ref "PS12V") (pin "A") (pinfunction "A_A") (pintype "passive"))
      (node (ref "R25") (pin "1") (pinfunction "1_1") (pintype "passive"))
    )
    (net (code "52") (name "PWM1-D2") (class "Default")
      (node (ref "FAN1") (pin "1") (pinfunction "1_1") (pintype "bidirectional"))
      (node (ref "NANO_33_IOT") (pin "D2") (pinfunction "D2_D2") (pintype "bidirectional"))
    )
    (net (code "53") (name "PWM2-D3") (class "Default")
      (node (ref "FAN2") (pin "1") (pinfunction "1_1") (pintype "bidirectional"))
      (node (ref "NANO_33_IOT") (pin "D3") (pinfunction "D3_D3") (pintype "bidirectional"))
    )
    (net (code "54") (name "SCK") (class "Default")
      (node (ref "IC2") (pin "13") (pinfunction "SCK_13") (pintype "bidirectional"))
      (node (ref "NANO_33_IOT") (pin "D13") (pinfunction "D13_D13") (pintype "bidirectional"))
    )
    (net (code "55") (name "SCL") (class "Default")
      (node (ref "IC4") (pin "4") (pinfunction "SCL_4") (pintype "bidirectional"))
      (node (ref "NANO_33_IOT") (pin "A5") (pinfunction "A5_A5") (pintype "bidirectional"))
      (node (ref "OLED") (pin "1") (pinfunction "1_1") (pintype "bidirectional"))
      (node (ref "SCL-N") (pin "2") (pinfunction "2_2") (pintype "passive"))
    )
    (net (code "56") (name "SCL-2") (class "Default")
      (node (ref "JP-N2") (pin "5") (pinfunction "5_5") (pintype "bidirectional"))
      (node (ref "SCL-N") (pin "1") (pinfunction "1_1") (pintype "passive"))
    )
    (net (code "57") (name "SCL-3") (class "Default")
      (node (ref "JP-N2") (pin "28") (pinfunction "28_28") (pintype "bidirectional"))
    )
    (net (code "58") (name "SDA") (class "Default")
      (node (ref "IC4") (pin "3") (pinfunction "SDA_3") (pintype "bidirectional"))
      (node (ref "NANO_33_IOT") (pin "A4") (pinfunction "A4_A4") (pintype "bidirectional"))
      (node (ref "OLED") (pin "2") (pinfunction "2_2") (pintype "bidirectional"))
      (node (ref "SDA-N") (pin "2") (pinfunction "2_2") (pintype "passive"))
    )
    (net (code "59") (name "SDA-2") (class "Default")
      (node (ref "JP-N2") (pin "3") (pinfunction "3_3") (pintype "bidirectional"))
      (node (ref "SDA-N") (pin "1") (pinfunction "1_1") (pintype "passive"))
    )
    (net (code "60") (name "SDA-3") (class "Default")
      (node (ref "JP-N2") (pin "27") (pinfunction "27_27") (pintype "bidirectional"))
    )
    (net (code "61") (name "SPI-INT") (class "Default")
      (node (ref "IC2") (pin "12") (pinfunction "~{INT}_12") (pintype "input"))
    )
    (net (code "62") (name "THERM-VO-SENS") (class "Default")
      (node (ref "NANO_33_IOT") (pin "A0") (pinfunction "A0_A0") (pintype "bidirectional"))
      (node (ref "R3") (pin "2") (pinfunction "2_2") (pintype "passive"))
      (node (ref "TEMP") (pin "2") (pinfunction "2_2") (pintype "passive"))
    )
    (net (code "63") (name "UART-CTS") (class "Default")
      (node (ref "JP-N2") (pin "29") (pinfunction "29_29") (pintype "bidirectional"))
    )
    (net (code "64") (name "UART-RTS") (class "Default")
      (node (ref "JP-N2") (pin "31") (pinfunction "31_31") (pintype "bidirectional"))
    )
    (net (code "65") (name "UART-RXD") (class "Default")
      (node (ref "JP-N2") (pin "10") (pinfunction "10_10") (pintype "bidirectional"))
    )
    (net (code "66") (name "UART-TXD") (class "Default")
      (node (ref "JP-N2") (pin "8") (pinfunction "8_8") (pintype "bidirectional"))
    )
    (net (code "67") (name "unconnected-(1/0-Pad1)") (class "Default")
      (node (ref "1/0") (pin "1") (pinfunction "1_1") (pintype "passive"))
    )
    (net (code "68") (name "unconnected-(FAN1-Pad2)") (class "Default")
      (node (ref "FAN1") (pin "2") (pinfunction "2_2") (pintype "bidirectional"))
    )
    (net (code "69") (name "unconnected-(FAN2-Pad2)") (class "Default")
      (node (ref "FAN2") (pin "2") (pinfunction "2_2") (pintype "bidirectional"))
    )
    (net (code "70") (name "unconnected-(IC2-CLKOUT{slash}SOF-Pad3)") (class "Default")
      (node (ref "IC2") (pin "3") (pinfunction "CLKOUT/SOF_3") (pintype "output"))
    )
    (net (code "71") (name "unconnected-(IC2-~{RX0BF}-Pad11)") (class "Default")
      (node (ref "IC2") (pin "11") (pinfunction "~{RX0BF}_11") (pintype "bidirectional"))
    )
    (net (code "72") (name "unconnected-(IC2-~{RX1BF}-Pad10)") (class "Default")
      (node (ref "IC2") (pin "10") (pinfunction "~{RX1BF}_10") (pintype "bidirectional"))
    )
    (net (code "73") (name "unconnected-(IC2-~{TX0RTS}-Pad4)") (class "Default")
      (node (ref "IC2") (pin "4") (pinfunction "~{TX0RTS}_4") (pintype "bidirectional"))
    )
    (net (code "74") (name "unconnected-(IC2-~{TX1RTS}-Pad5)") (class "Default")
      (node (ref "IC2") (pin "5") (pinfunction "~{TX1RTS}_5") (pintype "bidirectional"))
    )
    (net (code "75") (name "unconnected-(IC2-~{TX2RTS}-Pad6)") (class "Default")
      (node (ref "IC2") (pin "6") (pinfunction "~{TX2RTS}_6") (pintype "bidirectional"))
    )
    (net (code "76") (name "unconnected-(IC3-VREF-Pad5)") (class "Default")
      (node (ref "IC3") (pin "5") (pinfunction "VREF_5") (pintype "bidirectional"))
    )
    (net (code "77") (name "unconnected-(IC10-AIO0-Pad30)") (class "Default")
      (node (ref "IC10") (pin "30") (pinfunction "AIO0_30") (pintype "bidirectional"))
    )
    (net (code "78") (name "unconnected-(IC10-AIO1-Pad35)") (class "Default")
      (node (ref "IC10") (pin "35") (pinfunction "AIO1_35") (pintype "bidirectional"))
    )
    (net (code "79") (name "unconnected-(IC10-GPIO3-Pad20)") (class "Default")
      (node (ref "IC10") (pin "20") (pinfunction "GPIO3_20") (pintype "bidirectional"))
    )
    (net (code "80") (name "unconnected-(IC10-GPIO6-Pad3)") (class "Default")
      (node (ref "IC10") (pin "3") (pinfunction "GPIO6_3") (pintype "bidirectional"))
    )
    (net (code "81") (name "unconnected-(IC10-GPIO7-Pad4)") (class "Default")
      (node (ref "IC10") (pin "4") (pinfunction "GPIO7_4") (pintype "bidirectional"))
    )
    (net (code "82") (name "unconnected-(IC10-GPIO8-Pad31)") (class "Default")
      (node (ref "IC10") (pin "31") (pinfunction "GPIO8_31") (pintype "bidirectional"))
    )
    (net (code "83") (name "unconnected-(IC10-GPIO9-Pad32)") (class "Default")
      (node (ref "IC10") (pin "32") (pinfunction "GPIO9_32") (pintype "bidirectional"))
    )
    (net (code "84") (name "unconnected-(IC10-GPIO10-Pad33)") (class "Default")
      (node (ref "IC10") (pin "33") (pinfunction "GPIO10_33") (pintype "bidirectional"))
    )
    (net (code "85") (name "unconnected-(IC10-GPIO11-Pad34)") (class "Default")
      (node (ref "IC10") (pin "34") (pinfunction "GPIO11_34") (pintype "bidirectional"))
    )
    (net (code "86") (name "unconnected-(IC10-PCM_CLK-Pad7)") (class "Default")
      (node (ref "IC10") (pin "7") (pinfunction "PCM_CLK_7") (pintype "bidirectional"))
    )
    (net (code "87") (name "unconnected-(IC10-PCM_IN-Pad9)") (class "Default")
      (node (ref "IC10") (pin "9") (pinfunction "PCM_IN_9") (pintype "bidirectional"))
    )
    (net (code "88") (name "unconnected-(IC10-PCM_OUT-Pad10)") (class "Default")
      (node (ref "IC10") (pin "10") (pinfunction "PCM_OUT_10") (pintype "bidirectional"))
    )
    (net (code "89") (name "unconnected-(IC10-PCM_SYNC-Pad8)") (class "Default")
      (node (ref "IC10") (pin "8") (pinfunction "PCM_SYNC_8") (pintype "bidirectional"))
    )
    (net (code "90") (name "unconnected-(IC10-RESET-Pad5)") (class "Default")
      (node (ref "IC10") (pin "5") (pinfunction "RESET_5") (pintype "bidirectional"))
    )
    (net (code "91") (name "unconnected-(IC10-SPI_CLOCK-Pad6)") (class "Default")
      (node (ref "IC10") (pin "6") (pinfunction "SPI_CLOCK_6") (pintype "bidirectional"))
    )
    (net (code "92") (name "unconnected-(IC10-SPI_CSB-Pad23)") (class "Default")
      (node (ref "IC10") (pin "23") (pinfunction "SPI_CSB_23") (pintype "bidirectional"))
    )
    (net (code "93") (name "unconnected-(IC10-SPI_MISO-Pad24)") (class "Default")
      (node (ref "IC10") (pin "24") (pinfunction "SPI_MISO_24") (pintype "bidirectional"))
    )
    (net (code "94") (name "unconnected-(IC10-SPI_MOSI-Pad2)") (class "Default")
      (node (ref "IC10") (pin "2") (pinfunction "SPI_MOSI_2") (pintype "bidirectional"))
    )
    (net (code "95") (name "unconnected-(IC10-UART_CTS-Pad16)") (class "Default")
      (node (ref "IC10") (pin "16") (pinfunction "UART_CTS_16") (pintype "bidirectional"))
    )
    (net (code "96") (name "unconnected-(IC10-UART_RTS-Pad15)") (class "Default")
      (node (ref "IC10") (pin "15") (pinfunction "UART_RTS_15") (pintype "bidirectional"))
    )
    (net (code "97") (name "unconnected-(IC10-USB_D+-Pad17)") (class "Default")
      (node (ref "IC10") (pin "17") (pinfunction "USB_D+_17") (pintype "bidirectional"))
    )
    (net (code "98") (name "unconnected-(IC10-USB_D--Pad18)") (class "Default")
      (node (ref "IC10") (pin "18") (pinfunction "USB_D-_18") (pintype "bidirectional"))
    )
    (net (code "99") (name "unconnected-(JP-N2-Pad1)") (class "Default")
      (node (ref "JP-N2") (pin "1") (pinfunction "1_1") (pintype "bidirectional"))
    )
    (net (code "100") (name "unconnected-(JP-N2-Pad4)") (class "Default")
      (node (ref "JP-N2") (pin "4") (pinfunction "4_4") (pintype "bidirectional"))
    )
    (net (code "101") (name "unconnected-(JP-N2-Pad7)") (class "Default")
      (node (ref "JP-N2") (pin "7") (pinfunction "7_7") (pintype "bidirectional"))
    )
    (net (code "102") (name "unconnected-(JP-N2-Pad12)") (class "Default")
      (node (ref "JP-N2") (pin "12") (pinfunction "12_12") (pintype "bidirectional"))
    )
    (net (code "103") (name "unconnected-(JP-N2-Pad13)") (class "Default")
      (node (ref "JP-N2") (pin "13") (pinfunction "13_13") (pintype "bidirectional"))
    )
    (net (code "104") (name "unconnected-(JP-N2-Pad15)") (class "Default")
      (node (ref "JP-N2") (pin "15") (pinfunction "15_15") (pintype "bidirectional"))
    )
    (net (code "105") (name "unconnected-(JP-N2-Pad16)") (class "Default")
      (node (ref "JP-N2") (pin "16") (pinfunction "16_16") (pintype "bidirectional"))
    )
    (net (code "106") (name "unconnected-(JP-N2-Pad17)") (class "Default")
      (node (ref "JP-N2") (pin "17") (pinfunction "17_17") (pintype "bidirectional"))
    )
    (net (code "107") (name "unconnected-(JP-N2-Pad18)") (class "Default")
      (node (ref "JP-N2") (pin "18") (pinfunction "18_18") (pintype "bidirectional"))
    )
    (net (code "108") (name "unconnected-(JP-N2-Pad19)") (class "Default")
      (node (ref "JP-N2") (pin "19") (pinfunction "19_19") (pintype "bidirectional"))
    )
    (net (code "109") (name "unconnected-(JP-N2-Pad21)") (class "Default")
      (node (ref "JP-N2") (pin "21") (pinfunction "21_21") (pintype "bidirectional"))
    )
    (net (code "110") (name "unconnected-(JP-N2-Pad22)") (class "Default")
      (node (ref "JP-N2") (pin "22") (pinfunction "22_22") (pintype "bidirectional"))
    )
    (net (code "111") (name "unconnected-(JP-N2-Pad23)") (class "Default")
      (node (ref "JP-N2") (pin "23") (pinfunction "23_23") (pintype "bidirectional"))
    )
    (net (code "112") (name "unconnected-(JP-N2-Pad24)") (class "Default")
      (node (ref "JP-N2") (pin "24") (pinfunction "24_24") (pintype "bidirectional"))
    )
    (net (code "113") (name "unconnected-(JP-N2-Pad26)") (class "Default")
      (node (ref "JP-N2") (pin "26") (pinfunction "26_26") (pintype "bidirectional"))
    )
    (net (code "114") (name "unconnected-(JP-N2-Pad32)") (class "Default")
      (node (ref "JP-N2") (pin "32") (pinfunction "32_32") (pintype "bidirectional"))
    )
    (net (code "115") (name "unconnected-(JP-N2-Pad33)") (class "Default")
      (node (ref "JP-N2") (pin "33") (pinfunction "33_33") (pintype "bidirectional"))
    )
    (net (code "116") (name "unconnected-(JP-N2-Pad35)") (class "Default")
      (node (ref "JP-N2") (pin "35") (pinfunction "35_35") (pintype "bidirectional"))
    )
    (net (code "117") (name "unconnected-(JP-N2-Pad36)") (class "Default")
      (node (ref "JP-N2") (pin "36") (pinfunction "36_36") (pintype "bidirectional"))
    )
    (net (code "118") (name "unconnected-(JP-N2-Pad37)") (class "Default")
      (node (ref "JP-N2") (pin "37") (pinfunction "37_37") (pintype "bidirectional"))
    )
    (net (code "119") (name "unconnected-(JP-N2-Pad38)") (class "Default")
      (node (ref "JP-N2") (pin "38") (pinfunction "38_38") (pintype "bidirectional"))
    )
    (net (code "120") (name "unconnected-(JP-N2-Pad39)") (class "Default")
      (node (ref "JP-N2") (pin "39") (pinfunction "39_39") (pintype "bidirectional"))
    )
    (net (code "121") (name "unconnected-(JP-N2-Pad40)") (class "Default")
      (node (ref "JP-N2") (pin "40") (pinfunction "40_40") (pintype "bidirectional"))
    )
    (net (code "122") (name "unconnected-(NANO_33_IOT-PadRST$1)") (class "Default")
      (node (ref "NANO_33_IOT") (pin "RST$1") (pinfunction "RST$1_RST$1") (pintype "bidirectional"))
    )
    (net (code "123") (name "unconnected-(NANO_33_IOT-PadRST$2)") (class "Default")
      (node (ref "NANO_33_IOT") (pin "RST$2") (pinfunction "RST$2_RST$2") (pintype "bidirectional"))
    )
    (net (code "124") (name "unconnected-(NANO_33_IOT-PadVUSB)") (class "Default")
      (node (ref "NANO_33_IOT") (pin "VUSB") (pinfunction "VUSB_VUSB") (pintype "bidirectional"))
    )
    (net (code "125") (name "unconnected-(NANO_33_IOT-REF-PadAREF)") (class "Default")
      (node (ref "NANO_33_IOT") (pin "AREF") (pinfunction "REF_AREF") (pintype "bidirectional"))
    )
  )
)
